# BSB_ESP.net
KiCad netlist of a schematic drawn in EAGLE
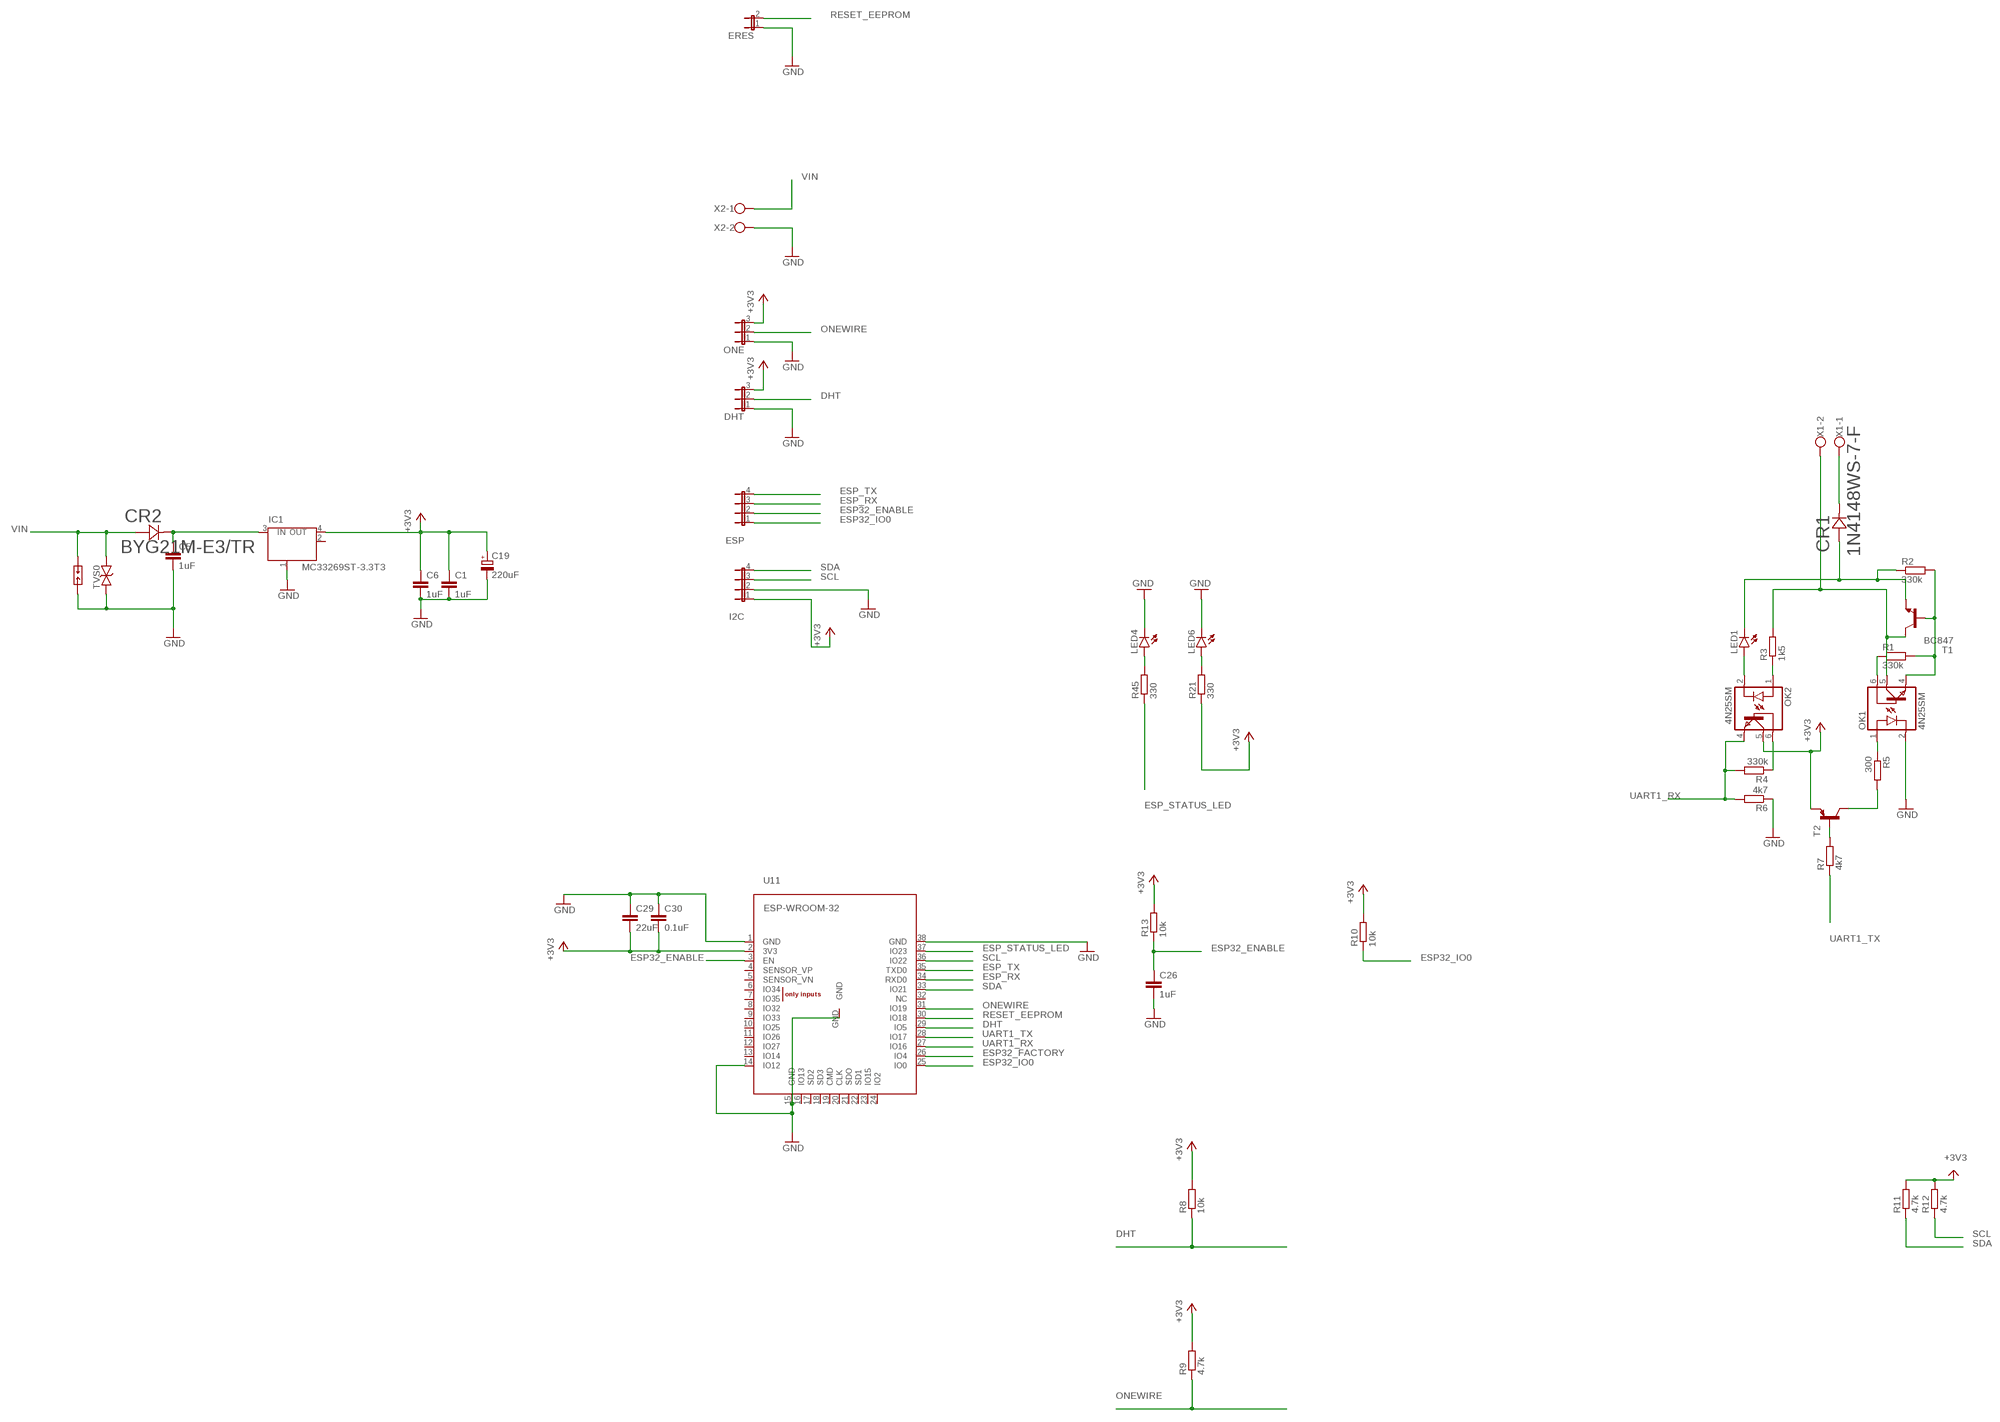
[diagram p0: schematic, sheet 1]

(export (version "E")
  (design (tool "Eeschema 10.0.6"))
  (components
    (comp (ref "C1")
      (value "1uF")
      (footprint "eagle-import:C1210")
      (libsource (lib "eagle-import") (part "C-EUC1210"))
    )
    (comp (ref "C5")
      (value "1uF")
      (footprint "eagle-import:C0805")
      (libsource (lib "eagle-import") (part "C-EUC0805"))
    )
    (comp (ref "C6")
      (value "1uF")
      (footprint "eagle-import:C0805")
      (libsource (lib "eagle-import") (part "C-EUC0805"))
    )
    (comp (ref "C19")
      (value "220uF")
      (footprint "eagle-import:153CLV-0807")
      (libsource (lib "eagle-import") (part "CPOL-EU153CLV-0807"))
    )
    (comp (ref "C26")
      (value "1uF")
      (footprint "eagle-import:C0603")
      (libsource (lib "eagle-import") (part "C-EUC0603"))
    )
    (comp (ref "C29")
      (value "22uF")
      (footprint "eagle-import:C0805")
      (libsource (lib "eagle-import") (part "C-EUC0805"))
    )
    (comp (ref "C30")
      (value "0.1uF")
      (footprint "eagle-import:C0805")
      (libsource (lib "eagle-import") (part "C-EUC0805"))
    )
    (comp (ref "CR1")
      (value "1N4148WS-7-F")
      (footprint "eagle-import:SOD323_DIO")
      (fields (field (name "COPYRIGHT") "Copyright (C) 2021 Ultra Librarian. All rights reserved."))
      (libsource (lib "eagle-import") (part "1N4148WS-7-F"))
    )
    (comp (ref "CR2")
      (value "BYG21M-E3/TR")
      (footprint "eagle-import:DO-214AC_VIS")
      (fields (field (name "COPYRIGHT") "Copyright (C) 2021 Ultra Librarian. All rights reserved."))
      (libsource (lib "eagle-import") (part "BYG21M-E3/TR"))
    )
    (comp (ref "DHT")
      (value "JP2E")
      (footprint "eagle-import:JP2")
      (libsource (lib "eagle-import") (part "JP2E"))
    )
    (comp (ref "ERES")
      (value "JP1E")
      (footprint "eagle-import:JP1")
      (libsource (lib "eagle-import") (part "JP1E"))
    )
    (comp (ref "ESP")
      (value "JP4E")
      (footprint "eagle-import:JP4")
      (libsource (lib "eagle-import") (part "JP4E"))
    )
    (comp (ref "I2C")
      (value "JP4E")
      (footprint "eagle-import:JP4")
      (libsource (lib "eagle-import") (part "JP4E"))
    )
    (comp (ref "IC1")
      (value "MC33269ST-3.3T3")
      (footprint "eagle-import:SOT223")
      (libsource (lib "eagle-import") (part "MC33269ST-3.3T3"))
    )
    (comp (ref "LED1")
      (value "LEDCHIP-LED0805")
      (footprint "eagle-import:CHIP-LED0805")
      (libsource (lib "eagle-import") (part "LEDCHIP-LED0805"))
    )
    (comp (ref "LED4")
      (value "LEDCHIP-LED0805")
      (footprint "eagle-import:CHIP-LED0805")
      (libsource (lib "eagle-import") (part "LEDCHIP-LED0805"))
    )
    (comp (ref "LED6")
      (value "LEDCHIP-LED0805")
      (footprint "eagle-import:CHIP-LED0805")
      (libsource (lib "eagle-import") (part "LEDCHIP-LED0805"))
    )
    (comp (ref "OK1")
      (value "4N25SM")
      (footprint "eagle-import:DIL6-SMD")
      (fields (field (name "MF") "FAIRCHILD SEMICONDUCTOR"))
      (libsource (lib "eagle-import") (part "4N?MS25"))
    )
    (comp (ref "OK2")
      (value "4N25SM")
      (footprint "eagle-import:DIL6-SMD")
      (fields (field (name "MF") "FAIRCHILD SEMICONDUCTOR"))
      (libsource (lib "eagle-import") (part "4N?MS25"))
    )
    (comp (ref "ONE")
      (value "JP2E")
      (footprint "eagle-import:JP2")
      (libsource (lib "eagle-import") (part "JP2E"))
    )
    (comp (ref "R1")
      (value "330k")
      (footprint "eagle-import:R0603")
      (libsource (lib "eagle-import") (part "R-EU_R0603"))
    )
    (comp (ref "R2")
      (value "330k")
      (footprint "eagle-import:R0603")
      (libsource (lib "eagle-import") (part "R-EU_R0603"))
    )
    (comp (ref "R3")
      (value "1k5")
      (footprint "eagle-import:R0603")
      (libsource (lib "eagle-import") (part "R-EU_R0603"))
    )
    (comp (ref "R4")
      (value "330k")
      (footprint "eagle-import:R0603")
      (libsource (lib "eagle-import") (part "R-EU_R0603"))
    )
    (comp (ref "R5")
      (value "300")
      (footprint "eagle-import:R0603")
      (libsource (lib "eagle-import") (part "R-EU_R0603"))
    )
    (comp (ref "R6")
      (value "4k7")
      (footprint "eagle-import:R0603")
      (libsource (lib "eagle-import") (part "R-EU_R0603"))
    )
    (comp (ref "R7")
      (value "4k7")
      (footprint "eagle-import:R0603")
      (libsource (lib "eagle-import") (part "R-EU_R0603"))
    )
    (comp (ref "R8")
      (value "10k")
      (footprint "eagle-import:R0402")
      (libsource (lib "eagle-import") (part "R-EU_R0402"))
    )
    (comp (ref "R9")
      (value "4.7k")
      (footprint "eagle-import:R0402")
      (libsource (lib "eagle-import") (part "R-EU_R0402"))
    )
    (comp (ref "R10")
      (value "10k")
      (footprint "eagle-import:R0603")
      (libsource (lib "eagle-import") (part "R-EU_R0603"))
    )
    (comp (ref "R11")
      (value "4.7k")
      (footprint "eagle-import:R0603")
      (libsource (lib "eagle-import") (part "R-EU_R0603"))
    )
    (comp (ref "R12")
      (value "4.7k")
      (footprint "eagle-import:R0603")
      (libsource (lib "eagle-import") (part "R-EU_R0603"))
    )
    (comp (ref "R13")
      (value "10k")
      (footprint "eagle-import:R0603")
      (libsource (lib "eagle-import") (part "R-EU_R0603"))
    )
    (comp (ref "R21")
      (value "330")
      (footprint "eagle-import:R0603")
      (libsource (lib "eagle-import") (part "R-EU_R0603"))
    )
    (comp (ref "R45")
      (value "330")
      (footprint "eagle-import:R0603")
      (libsource (lib "eagle-import") (part "R-EU_R0603"))
    )
    (comp (ref "SP0")
      (value "PCB-SGAP")
      (footprint "eagle-import:PCB-SGAP")
      (libsource (lib "eagle-import") (part "PCB-SGAP"))
    )
    (comp (ref "T1")
      (value "BC847")
      (footprint "eagle-import:SOT23")
      (libsource (lib "eagle-import") (part "BC847"))
    )
    (comp (ref "T2")
      (value "BC857A-PNP-SOT23-BEC")
      (footprint "eagle-import:SOT23-BEC")
      (libsource (lib "eagle-import") (part "-PNP-SOT23-BECBC857A"))
    )
    (comp (ref "TVS0")
      (value "43CA")
      (footprint "eagle-import:SMB")
      (libsource (lib "eagle-import") (part "DIODE-BTVSSMB"))
    )
    (comp (ref "U11")
      (value "ESP-WROOM-32")
      (footprint "eagle-import:ESP-WROOM-32")
      (libsource (lib "eagle-import") (part "ESP-WROOM-32"))
    )
    (comp (ref "X1")
      (value "W237-102")
      (footprint "eagle-import:W237-102")
      (fields (field (name "MPN") "237-102"))
      (libsource (lib "eagle-import") (part "W237-102"))
    )
    (comp (ref "X2")
      (value "W237-102")
      (footprint "eagle-import:W237-102")
      (fields (field (name "MPN") "237-102"))
      (libsource (lib "eagle-import") (part "W237-102"))
    )
  )
  (nets
    (net (code "1") (name "+3V3") (class "Default")
      (node (ref "C1") (pin "1") (pinfunction "1_1") (pintype "passive"))
      (node (ref "C19") (pin "+") (pinfunction "+_+") (pintype "passive"))
      (node (ref "C29") (pin "2") (pinfunction "2_2") (pintype "passive"))
      (node (ref "C30") (pin "2") (pinfunction "2_2") (pintype "passive"))
      (node (ref "C6") (pin "1") (pinfunction "1_1") (pintype "passive"))
      (node (ref "DHT") (pin "3") (pinfunction "3_3") (pintype "passive"))
      (node (ref "I2C") (pin "1") (pinfunction "1_1") (pintype "passive"))
      (node (ref "IC1") (pin "4") (pinfunction "OUT_4") (pintype "passive"))
      (node (ref "OK2") (pin "5") (pinfunction "COL_5") (pintype "passive"))
      (node (ref "ONE") (pin "3") (pinfunction "3_3") (pintype "passive"))
      (node (ref "R10") (pin "2") (pinfunction "2_2") (pintype "passive"))
      (node (ref "R11") (pin "2") (pinfunction "2_2") (pintype "passive"))
      (node (ref "R12") (pin "2") (pinfunction "2_2") (pintype "passive"))
      (node (ref "R13") (pin "2") (pinfunction "2_2") (pintype "passive"))
      (node (ref "R21") (pin "1") (pinfunction "1_1") (pintype "passive"))
      (node (ref "R8") (pin "2") (pinfunction "2_2") (pintype "passive"))
      (node (ref "R9") (pin "2") (pinfunction "2_2") (pintype "passive"))
      (node (ref "T2") (pin "E") (pinfunction "E_E") (pintype "passive"))
      (node (ref "U11") (pin "2") (pinfunction "3V3_2") (pintype "bidirectional"))
    )
    (net (code "2") (name "/DHT") (class "Default")
      (node (ref "DHT") (pin "2") (pinfunction "2_2") (pintype "passive"))
      (node (ref "R8") (pin "1") (pinfunction "1_1") (pintype "passive"))
      (node (ref "U11") (pin "29") (pinfunction "IO5_29") (pintype "bidirectional"))
    )
    (net (code "3") (name "/ESP32_ENABLE") (class "Default")
      (node (ref "C26") (pin "1") (pinfunction "1_1") (pintype "passive"))
      (node (ref "ESP") (pin "2") (pinfunction "2_2") (pintype "passive"))
      (node (ref "R13") (pin "1") (pinfunction "1_1") (pintype "passive"))
      (node (ref "U11") (pin "3") (pinfunction "EN_3") (pintype "bidirectional"))
    )
    (net (code "4") (name "/ESP32_FACTORY") (class "Default")
      (node (ref "U11") (pin "26") (pinfunction "IO4_26") (pintype "bidirectional"))
    )
    (net (code "5") (name "/ESP32_IO0") (class "Default")
      (node (ref "ESP") (pin "1") (pinfunction "1_1") (pintype "passive"))
      (node (ref "R10") (pin "1") (pinfunction "1_1") (pintype "passive"))
      (node (ref "U11") (pin "25") (pinfunction "IO0_25") (pintype "bidirectional"))
    )
    (net (code "6") (name "/ESP_RX") (class "Default")
      (node (ref "ESP") (pin "3") (pinfunction "3_3") (pintype "passive"))
      (node (ref "U11") (pin "34") (pinfunction "RXD0_34") (pintype "bidirectional"))
    )
    (net (code "7") (name "/ESP_STATUS_LED") (class "Default")
      (node (ref "R45") (pin "1") (pinfunction "1_1") (pintype "passive"))
      (node (ref "U11") (pin "37") (pinfunction "IO23_37") (pintype "bidirectional"))
    )
    (net (code "8") (name "/ESP_TX") (class "Default")
      (node (ref "ESP") (pin "4") (pinfunction "4_4") (pintype "passive"))
      (node (ref "U11") (pin "35") (pinfunction "TXD0_35") (pintype "bidirectional"))
    )
    (net (code "9") (name "/ONEWIRE") (class "Default")
      (node (ref "ONE") (pin "2") (pinfunction "2_2") (pintype "passive"))
      (node (ref "R9") (pin "1") (pinfunction "1_1") (pintype "passive"))
      (node (ref "U11") (pin "31") (pinfunction "IO19_31") (pintype "bidirectional"))
    )
    (net (code "10") (name "/RESET_EEPROM") (class "Default")
      (node (ref "ERES") (pin "2") (pinfunction "2_2") (pintype "passive"))
      (node (ref "U11") (pin "30") (pinfunction "IO18_30") (pintype "bidirectional"))
    )
    (net (code "11") (name "/SCL") (class "Default")
      (node (ref "I2C") (pin "3") (pinfunction "3_3") (pintype "passive"))
      (node (ref "R12") (pin "1") (pinfunction "1_1") (pintype "passive"))
      (node (ref "U11") (pin "36") (pinfunction "IO22_36") (pintype "bidirectional"))
    )
    (net (code "12") (name "/SDA") (class "Default")
      (node (ref "I2C") (pin "4") (pinfunction "4_4") (pintype "passive"))
      (node (ref "R11") (pin "1") (pinfunction "1_1") (pintype "passive"))
      (node (ref "U11") (pin "33") (pinfunction "IO21_33") (pintype "bidirectional"))
    )
    (net (code "13") (name "/UART1_RX") (class "Default")
      (node (ref "OK2") (pin "4") (pinfunction "EMI_4") (pintype "passive"))
      (node (ref "R4") (pin "2") (pinfunction "2_2") (pintype "passive"))
      (node (ref "R6") (pin "2") (pinfunction "2_2") (pintype "passive"))
      (node (ref "U11") (pin "27") (pinfunction "IO16_27") (pintype "bidirectional"))
    )
    (net (code "14") (name "/UART1_TX") (class "Default")
      (node (ref "R7") (pin "1") (pinfunction "1_1") (pintype "passive"))
      (node (ref "U11") (pin "28") (pinfunction "IO17_28") (pintype "bidirectional"))
    )
    (net (code "15") (name "/VIN") (class "Default")
      (node (ref "CR2") (pin "2") (pinfunction "2_2") (pintype "passive"))
      (node (ref "SP0") (pin "1") (pinfunction "1_1") (pintype "passive"))
      (node (ref "TVS0") (pin "C") (pinfunction "C_C") (pintype "passive"))
      (node (ref "X2") (pin "1") (pinfunction "KL_1") (pintype "passive"))
    )
    (net (code "16") (name "GND") (class "Default")
      (node (ref "C1") (pin "2") (pinfunction "2_2") (pintype "passive"))
      (node (ref "C19") (pin "-") (pinfunction "-_-") (pintype "passive"))
      (node (ref "C26") (pin "2") (pinfunction "2_2") (pintype "passive"))
      (node (ref "C29") (pin "1") (pinfunction "1_1") (pintype "passive"))
      (node (ref "C30") (pin "1") (pinfunction "1_1") (pintype "passive"))
      (node (ref "C5") (pin "2") (pinfunction "2_2") (pintype "passive"))
      (node (ref "C6") (pin "2") (pinfunction "2_2") (pintype "passive"))
      (node (ref "DHT") (pin "1") (pinfunction "1_1") (pintype "passive"))
      (node (ref "ERES") (pin "1") (pinfunction "1_1") (pintype "passive"))
      (node (ref "I2C") (pin "2") (pinfunction "2_2") (pintype "passive"))
      (node (ref "IC1") (pin "1") (pinfunction "GND/ADJ_1") (pintype "input"))
      (node (ref "LED4") (pin "C") (pinfunction "C_C") (pintype "passive"))
      (node (ref "LED6") (pin "C") (pinfunction "C_C") (pintype "passive"))
      (node (ref "OK1") (pin "2") (pinfunction "C_2") (pintype "passive"))
      (node (ref "ONE") (pin "1") (pinfunction "1_1") (pintype "passive"))
      (node (ref "R6") (pin "1") (pinfunction "1_1") (pintype "passive"))
      (node (ref "SP0") (pin "2") (pinfunction "2_2") (pintype "passive"))
      (node (ref "TVS0") (pin "A") (pinfunction "A_A") (pintype "passive"))
      (node (ref "U11") (pin "1") (pinfunction "GND_1") (pintype "bidirectional"))
      (node (ref "U11") (pin "14") (pinfunction "IO12_14") (pintype "bidirectional"))
      (node (ref "U11") (pin "15") (pinfunction "GND_15") (pintype "bidirectional"))
      (node (ref "U11") (pin "38") (pinfunction "GND_38") (pintype "bidirectional"))
      (node (ref "U11") (pin "GND") (pinfunction "GND_GND") (pintype "bidirectional"))
      (node (ref "X2") (pin "2") (pinfunction "KL_2") (pintype "passive"))
    )
    (net (code "17") (name "Net-(IC1-IN)") (class "Default")
      (node (ref "C5") (pin "1") (pinfunction "1_1") (pintype "passive"))
      (node (ref "CR2") (pin "1") (pinfunction "1_1") (pintype "passive"))
      (node (ref "IC1") (pin "3") (pinfunction "IN_3") (pintype "input"))
    )
    (net (code "18") (name "Net-(LED4-PadA)") (class "Default")
      (node (ref "LED4") (pin "A") (pinfunction "A_A") (pintype "passive"))
      (node (ref "R45") (pin "2") (pinfunction "2_2") (pintype "passive"))
    )
    (net (code "19") (name "Net-(LED6-PadA)") (class "Default")
      (node (ref "LED6") (pin "A") (pinfunction "A_A") (pintype "passive"))
      (node (ref "R21") (pin "2") (pinfunction "2_2") (pintype "passive"))
    )
    (net (code "20") (name "Net-(OK1-A)") (class "Default")
      (node (ref "OK1") (pin "1") (pinfunction "A_1") (pintype "passive"))
      (node (ref "R5") (pin "1") (pinfunction "1_1") (pintype "passive"))
    )
    (net (code "21") (name "Net-(OK1-BAS)") (class "Default")
      (node (ref "OK1") (pin "6") (pinfunction "BAS_6") (pintype "passive"))
      (node (ref "R1") (pin "1") (pinfunction "1_1") (pintype "passive"))
    )
    (net (code "22") (name "Net-(OK1-COL)") (class "Default")
      (node (ref "OK1") (pin "5") (pinfunction "COL_5") (pintype "passive"))
      (node (ref "R3") (pin "2") (pinfunction "2_2") (pintype "passive"))
      (node (ref "T1") (pin "3") (pinfunction "C_3") (pintype "passive"))
      (node (ref "X1") (pin "2") (pinfunction "KL_2") (pintype "passive"))
    )
    (net (code "23") (name "Net-(OK1-EMI)") (class "Default")
      (node (ref "OK1") (pin "4") (pinfunction "EMI_4") (pintype "passive"))
      (node (ref "R1") (pin "2") (pinfunction "2_2") (pintype "passive"))
      (node (ref "R2") (pin "2") (pinfunction "2_2") (pintype "passive"))
      (node (ref "T1") (pin "1") (pinfunction "B_1") (pintype "passive"))
    )
    (net (code "24") (name "Net-(OK2-A)") (class "Default")
      (node (ref "OK2") (pin "1") (pinfunction "A_1") (pintype "passive"))
      (node (ref "R3") (pin "1") (pinfunction "1_1") (pintype "passive"))
    )
    (net (code "25") (name "Net-(OK2-BAS)") (class "Default")
      (node (ref "OK2") (pin "6") (pinfunction "BAS_6") (pintype "passive"))
      (node (ref "R4") (pin "1") (pinfunction "1_1") (pintype "passive"))
    )
    (net (code "26") (name "Net-(OK2-C)") (class "Default")
      (node (ref "LED1") (pin "A") (pinfunction "A_A") (pintype "passive"))
      (node (ref "OK2") (pin "2") (pinfunction "C_2") (pintype "passive"))
    )
    (net (code "27") (name "Net-(R5-Pad2)") (class "Default")
      (node (ref "R5") (pin "2") (pinfunction "2_2") (pintype "passive"))
      (node (ref "T2") (pin "C") (pinfunction "C_C") (pintype "passive"))
    )
    (net (code "28") (name "Net-(R7-Pad2)") (class "Default")
      (node (ref "R7") (pin "2") (pinfunction "2_2") (pintype "passive"))
      (node (ref "T2") (pin "B") (pinfunction "B_B") (pintype "passive"))
    )
    (net (code "29") (name "Net-(T1-E)") (class "Default")
      (node (ref "CR1") (pin "2") (pinfunction "2_2") (pintype "passive"))
      (node (ref "LED1") (pin "C") (pinfunction "C_C") (pintype "passive"))
      (node (ref "R2") (pin "1") (pinfunction "1_1") (pintype "passive"))
      (node (ref "T1") (pin "2") (pinfunction "E_2") (pintype "passive"))
    )
    (net (code "30") (name "Net-(X1A-KL)") (class "Default")
      (node (ref "CR1") (pin "1") (pinfunction "1_1") (pintype "passive"))
      (node (ref "X1") (pin "1") (pinfunction "KL_1") (pintype "passive"))
    )
    (net (code "31") (name "unconnected-(IC1-OUT-Pad2)") (class "Default")
      (node (ref "IC1") (pin "2") (pinfunction "OUT_2") (pintype "passive"))
    )
    (net (code "32") (name "unconnected-(U11-CLK-Pad20)") (class "Default")
      (node (ref "U11") (pin "20") (pinfunction "CLK_20") (pintype "bidirectional"))
    )
    (net (code "33") (name "unconnected-(U11-CMD-Pad19)") (class "Default")
      (node (ref "U11") (pin "19") (pinfunction "CMD_19") (pintype "bidirectional"))
    )
    (net (code "34") (name "unconnected-(U11-IO2-Pad24)") (class "Default")
      (node (ref "U11") (pin "24") (pinfunction "IO2_24") (pintype "bidirectional"))
    )
    (net (code "35") (name "unconnected-(U11-IO13-Pad16)") (class "Default")
      (node (ref "U11") (pin "16") (pinfunction "IO13_16") (pintype "bidirectional"))
    )
    (net (code "36") (name "unconnected-(U11-IO14-Pad13)") (class "Default")
      (node (ref "U11") (pin "13") (pinfunction "IO14_13") (pintype "bidirectional"))
    )
    (net (code "37") (name "unconnected-(U11-IO15-Pad23)") (class "Default")
      (node (ref "U11") (pin "23") (pinfunction "IO15_23") (pintype "bidirectional"))
    )
    (net (code "38") (name "unconnected-(U11-IO25-Pad10)") (class "Default")
      (node (ref "U11") (pin "10") (pinfunction "IO25_10") (pintype "bidirectional"))
    )
    (net (code "39") (name "unconnected-(U11-IO26-Pad11)") (class "Default")
      (node (ref "U11") (pin "11") (pinfunction "IO26_11") (pintype "bidirectional"))
    )
    (net (code "40") (name "unconnected-(U11-IO27-Pad12)") (class "Default")
      (node (ref "U11") (pin "12") (pinfunction "IO27_12") (pintype "bidirectional"))
    )
    (net (code "41") (name "unconnected-(U11-IO32-Pad8)") (class "Default")
      (node (ref "U11") (pin "8") (pinfunction "IO32_8") (pintype "bidirectional"))
    )
    (net (code "42") (name "unconnected-(U11-IO33-Pad9)") (class "Default")
      (node (ref "U11") (pin "9") (pinfunction "IO33_9") (pintype "bidirectional"))
    )
    (net (code "43") (name "unconnected-(U11-IO34-Pad6)") (class "Default")
      (node (ref "U11") (pin "6") (pinfunction "IO34_6") (pintype "input"))
    )
    (net (code "44") (name "unconnected-(U11-IO35-Pad7)") (class "Default")
      (node (ref "U11") (pin "7") (pinfunction "IO35_7") (pintype "input"))
    )
    (net (code "45") (name "unconnected-(U11-NC-Pad32)") (class "Default")
      (node (ref "U11") (pin "32") (pinfunction "NC_32") (pintype "bidirectional"))
    )
    (net (code "46") (name "unconnected-(U11-SD1-Pad22)") (class "Default")
      (node (ref "U11") (pin "22") (pinfunction "SD1_22") (pintype "bidirectional"))
    )
    (net (code "47") (name "unconnected-(U11-SD2-Pad17)") (class "Default")
      (node (ref "U11") (pin "17") (pinfunction "SD2_17") (pintype "bidirectional"))
    )
    (net (code "48") (name "unconnected-(U11-SD3-Pad18)") (class "Default")
      (node (ref "U11") (pin "18") (pinfunction "SD3_18") (pintype "bidirectional"))
    )
    (net (code "49") (name "unconnected-(U11-SDO-Pad21)") (class "Default")
      (node (ref "U11") (pin "21") (pinfunction "SDO_21") (pintype "bidirectional"))
    )
    (net (code "50") (name "unconnected-(U11-SENSOR_VN-Pad5)") (class "Default")
      (node (ref "U11") (pin "5") (pinfunction "SENSOR_VN_5") (pintype "input"))
    )
    (net (code "51") (name "unconnected-(U11-SENSOR_VP-Pad4)") (class "Default")
      (node (ref "U11") (pin "4") (pinfunction "SENSOR_VP_4") (pintype "input"))
    )
  )
)
